# WPT_PLL_Transmitter.net
KiCad netlist of a schematic drawn in Altium Designer
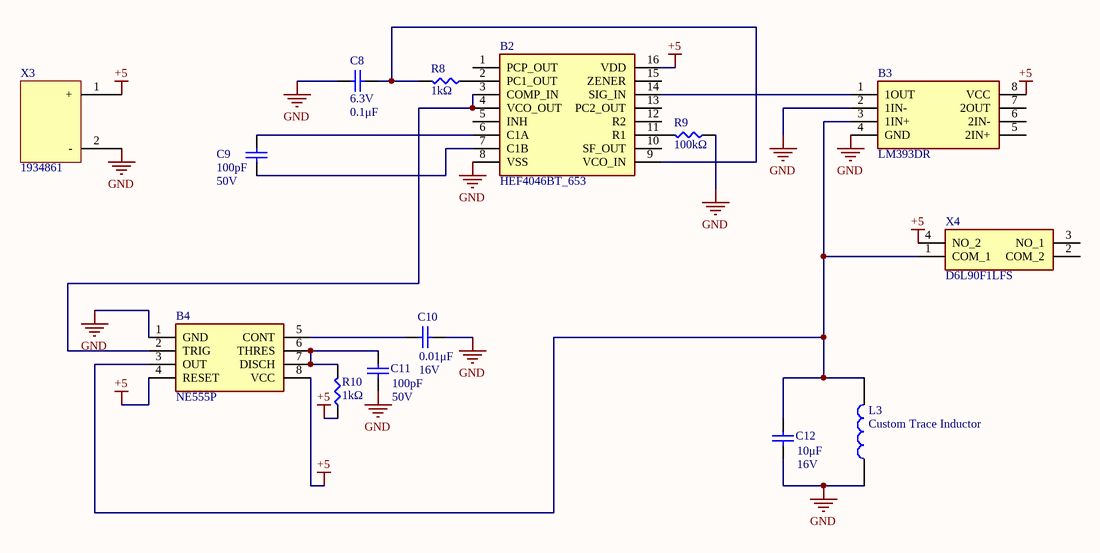
[diagram p0: WPT_PLL_Transmitter.SchDoc]

(export (version "E")
  (design (tool "Eeschema 10.0.6"))
  (components
    (comp (ref "B2")
      (value "HEF4046BT_653")
      (footprint "HEF4046BT653")
      (description "HEF4046B - Phase-locked loop@en-us")
      (fields
        (field (name "MOUSER PART NUMBER") "771-HEF4046BTD-T")
        (field (name "MANUFACTURER_PART_NUMBER") "HEF4046BT,653")
      )
      (libsource (lib "Bootcamp_Schematic_Library") (part "HEF4046BT_653"))
    )
    (comp (ref "B3")
      (value "LM393DR")
      (footprint "SOIC127P600X175-8N")
      (fields (field (name "MOUSER PART NUMBER") "595-LM393DR"))
      (libsource (lib "Bootcamp_Schematic_Library") (part "LM393DR"))
    )
    (comp (ref "B4")
      (value "NE555P")
      (footprint "DIP794W53P254L959H508Q8N")
      (fields (field (name "MOUSER PART NUMBER") "595-NE555P"))
      (libsource (lib "Bootcamp_Schematic_Library") (part "NE555P_1"))
    )
    (comp (ref "C8")
      (value "0.1μF")
      (footprint "CAP0201")
      (description "CAP CER 0.1UF 6.3V X5R 0201")
      (fields (field (name "VOLTAGE RATING") "6.3V") (field (name "Comment") "CL03A104KQ3NNNC"))
      (libsource (lib "Bootcamp_Schematic_Library") (part "CL03A104KQ3NNNC"))
    )
    (comp (ref "C9")
      (value "100pF")
      (footprint "CAP0201")
      (description "CAP CER 100PF 50V C0G/NP0 0201")
      (fields (field (name "VOLTAGE RATING") "50V") (field (name "Comment") "GCM0335C1H101FA16D"))
      (libsource (lib "Bootcamp_Schematic_Library") (part "GCM0335C1H101FA16D"))
    )
    (comp (ref "C10")
      (value "0.01μF")
      (footprint "CAP0402")
      (description "CAP CER 10000PF 16V X7R 0402")
      (fields (field (name "VOLTAGE RATING") "16V") (field (name "Comment") "KGM05AR71C103KH"))
      (libsource (lib "Bootcamp_Schematic_Library") (part "KGM05AR71C103KH"))
    )
    (comp (ref "C11")
      (value "100pF")
      (footprint "CAP0201")
      (description "CAP CER 100PF 50V C0G/NP0 0201")
      (fields (field (name "VOLTAGE RATING") "50V") (field (name "Comment") "GCM0335C1H101FA16D"))
      (libsource (lib "Bootcamp_Schematic_Library") (part "GCM0335C1H101FA16D"))
    )
    (comp (ref "C12")
      (value "10μF")
      (footprint "CAP0805")
      (description "CAP CER 10UF 16V X5R 0805")
      (fields (field (name "VOLTAGE RATING") "16V") (field (name "Comment") "CL21A106KOCLRNC"))
      (libsource (lib "Bootcamp_Schematic_Library") (part "CL21A106KOCLRNC"))
    )
    (comp (ref "L3")
      (value "Custom Trace Inductor")
      (footprint "Custom Trace Inductor")
      (fields
        (field (name "MOUSER PART NUMBER") "652-SRN3015-2R2M")
        (field (name "MANUFACTURER_PART_NUMBER") "SRN3015-2R2M")
      )
      (libsource (lib "Bootcamp_Schematic_Library") (part "Custom Trace Inductor"))
    )
    (comp (ref "R8")
      (value "1kΩ")
      (footprint "RES1206")
      (description "RES 1K OHM 1% 1/2W 1206")
      (fields (field (name "Comment") "RNCP1206FTD1K00"))
      (libsource (lib "Bootcamp_Schematic_Library") (part "RNCP1206FTD1K00"))
    )
    (comp (ref "R9")
      (value "100kΩ")
      (footprint "RES0603")
      (description "RES 100K OHM 1% 1/10W 0603")
      (fields (field (name "Comment") "RC0603FR-07100KL"))
      (libsource (lib "Bootcamp_Schematic_Library") (part "RC0603FR-07100KL"))
    )
    (comp (ref "R10")
      (value "1kΩ")
      (footprint "RES1206")
      (description "RES 1K OHM 1% 1/2W 1206")
      (fields (field (name "Comment") "RNCP1206FTD1K00"))
      (libsource (lib "Bootcamp_Schematic_Library") (part "RNCP1206FTD1K00"))
    )
    (comp (ref "X3")
      (value "1934861")
      (footprint "1934861")
      (libsource (lib "Bootcamp_Schematic_Library") (part "1934861"))
    )
    (comp (ref "X4")
      (value "D6L90F1LFS")
      (footprint "D6L90F1LFS")
      (description "Pushbutton Switches Key Switch N.O. SPDT 100 mA")
      (fields (field (name "MOUSER PART NUMBER") "611-D6L90F1LFS"))
      (libsource (lib "Bootcamp_Schematic_Library") (part "D6L90F1LFS"))
    )
  )
  (nets
    (net (code "1") (name "+5") (class "Default")
      (node (ref "B2") (pin "16") (pinfunction "VDD_16") (pintype "passive"))
      (node (ref "B3") (pin "8") (pinfunction "VCC_8") (pintype "passive"))
      (node (ref "B4") (pin "4") (pinfunction "RESET_4") (pintype "passive"))
      (node (ref "B4") (pin "8") (pinfunction "VCC_8") (pintype "passive"))
      (node (ref "R10") (pin "2") (pinfunction "2_2") (pintype "passive"))
      (node (ref "X3") (pin "1") (pinfunction "+_1") (pintype "passive"))
      (node (ref "X4") (pin "4") (pinfunction "NO_2_4") (pintype "passive"))
    )
    (net (code "2") (name "GND") (class "Default")
      (node (ref "B2") (pin "8") (pinfunction "VSS_8") (pintype "passive"))
      (node (ref "B3") (pin "2") (pinfunction "1IN-_2") (pintype "passive"))
      (node (ref "B3") (pin "4") (pinfunction "GND_4") (pintype "passive"))
      (node (ref "B4") (pin "1") (pinfunction "GND_1") (pintype "passive"))
      (node (ref "C10") (pin "2") (pinfunction "2_2") (pintype "passive"))
      (node (ref "C11") (pin "2") (pinfunction "2_2") (pintype "passive"))
      (node (ref "C12") (pin "1") (pinfunction "1_1") (pintype "passive"))
      (node (ref "C8") (pin "1") (pinfunction "1_1") (pintype "passive"))
      (node (ref "L3") (pin "1") (pinfunction "1_1") (pintype "passive"))
      (node (ref "R9") (pin "2") (pinfunction "2_2") (pintype "passive"))
      (node (ref "X3") (pin "2") (pinfunction "-_2") (pintype "passive"))
    )
    (net (code "3") (name "Net-(B2-C1A)") (class "Default")
      (node (ref "B2") (pin "6") (pinfunction "C1A_6") (pintype "passive"))
      (node (ref "C9") (pin "2") (pinfunction "2_2") (pintype "passive"))
    )
    (net (code "4") (name "Net-(B2-C1B)") (class "Default")
      (node (ref "B2") (pin "7") (pinfunction "C1B_7") (pintype "passive"))
      (node (ref "C9") (pin "1") (pinfunction "1_1") (pintype "passive"))
    )
    (net (code "5") (name "Net-(B2-COMP_IN)") (class "Default")
      (node (ref "B2") (pin "3") (pinfunction "COMP_IN_3") (pintype "passive"))
      (node (ref "B2") (pin "4") (pinfunction "VCO_OUT_4") (pintype "passive"))
      (node (ref "B4") (pin "2") (pinfunction "TRIG_2") (pintype "passive"))
    )
    (net (code "6") (name "Net-(B2-PC1_OUT)") (class "Default")
      (node (ref "B2") (pin "2") (pinfunction "PC1_OUT_2") (pintype "passive"))
      (node (ref "R8") (pin "2") (pinfunction "2_2") (pintype "passive"))
    )
    (net (code "7") (name "Net-(B2-R1)") (class "Default")
      (node (ref "B2") (pin "11") (pinfunction "R1_11") (pintype "passive"))
      (node (ref "R9") (pin "1") (pinfunction "1_1") (pintype "passive"))
    )
    (net (code "8") (name "Net-(B2-SIG_IN)") (class "Default")
      (node (ref "B2") (pin "14") (pinfunction "SIG_IN_14") (pintype "passive"))
      (node (ref "B3") (pin "1") (pinfunction "1OUT_1") (pintype "passive"))
    )
    (net (code "9") (name "Net-(B2-VCO_IN)") (class "Default")
      (node (ref "B2") (pin "9") (pinfunction "VCO_IN_9") (pintype "passive"))
      (node (ref "C8") (pin "2") (pinfunction "2_2") (pintype "passive"))
      (node (ref "R8") (pin "1") (pinfunction "1_1") (pintype "passive"))
    )
    (net (code "10") (name "Net-(B3-1IN+)") (class "Default")
      (node (ref "B3") (pin "3") (pinfunction "1IN+_3") (pintype "passive"))
      (node (ref "B4") (pin "3") (pinfunction "OUT_3") (pintype "passive"))
      (node (ref "C12") (pin "2") (pinfunction "2_2") (pintype "passive"))
      (node (ref "L3") (pin "2") (pinfunction "2_2") (pintype "passive"))
      (node (ref "X4") (pin "1") (pinfunction "COM_1_1") (pintype "passive"))
    )
    (net (code "11") (name "Net-(B4-CONT)") (class "Default")
      (node (ref "B4") (pin "5") (pinfunction "CONT_5") (pintype "passive"))
      (node (ref "C10") (pin "1") (pinfunction "1_1") (pintype "passive"))
    )
    (net (code "12") (name "Net-(B4-DISCH)") (class "Default")
      (node (ref "B4") (pin "6") (pinfunction "THRES_6") (pintype "passive"))
      (node (ref "B4") (pin "7") (pinfunction "DISCH_7") (pintype "passive"))
      (node (ref "C11") (pin "1") (pinfunction "1_1") (pintype "passive"))
      (node (ref "R10") (pin "1") (pinfunction "1_1") (pintype "passive"))
    )
    (net (code "13") (name "unconnected-(B2-INH-Pad5)") (class "Default")
      (node (ref "B2") (pin "5") (pinfunction "INH_5") (pintype "passive"))
    )
    (net (code "14") (name "unconnected-(B2-PC2_OUT-Pad13)") (class "Default")
      (node (ref "B2") (pin "13") (pinfunction "PC2_OUT_13") (pintype "passive"))
    )
    (net (code "15") (name "unconnected-(B2-PCP_OUT-Pad1)") (class "Default")
      (node (ref "B2") (pin "1") (pinfunction "PCP_OUT_1") (pintype "passive"))
    )
    (net (code "16") (name "unconnected-(B2-R2-Pad12)") (class "Default")
      (node (ref "B2") (pin "12") (pinfunction "R2_12") (pintype "passive"))
    )
    (net (code "17") (name "unconnected-(B2-SF_OUT-Pad10)") (class "Default")
      (node (ref "B2") (pin "10") (pinfunction "SF_OUT_10") (pintype "passive"))
    )
    (net (code "18") (name "unconnected-(B2-ZENER-Pad15)") (class "Default")
      (node (ref "B2") (pin "15") (pinfunction "ZENER_15") (pintype "passive"))
    )
    (net (code "19") (name "unconnected-(B3-2IN+-Pad5)") (class "Default")
      (node (ref "B3") (pin "5") (pinfunction "2IN+_5") (pintype "passive"))
    )
    (net (code "20") (name "unconnected-(B3-2IN--Pad6)") (class "Default")
      (node (ref "B3") (pin "6") (pinfunction "2IN-_6") (pintype "passive"))
    )
    (net (code "21") (name "unconnected-(B3-2OUT-Pad7)") (class "Default")
      (node (ref "B3") (pin "7") (pinfunction "2OUT_7") (pintype "passive"))
    )
    (net (code "22") (name "unconnected-(X4-COM_2-Pad2)") (class "Default")
      (node (ref "X4") (pin "2") (pinfunction "COM_2_2") (pintype "passive"))
    )
    (net (code "23") (name "unconnected-(X4-NO_1-Pad3)") (class "Default")
      (node (ref "X4") (pin "3") (pinfunction "NO_1_3") (pintype "passive"))
    )
  )
)
